# activity_monitor_v1.net
KiCad netlist of a schematic drawn in EAGLE
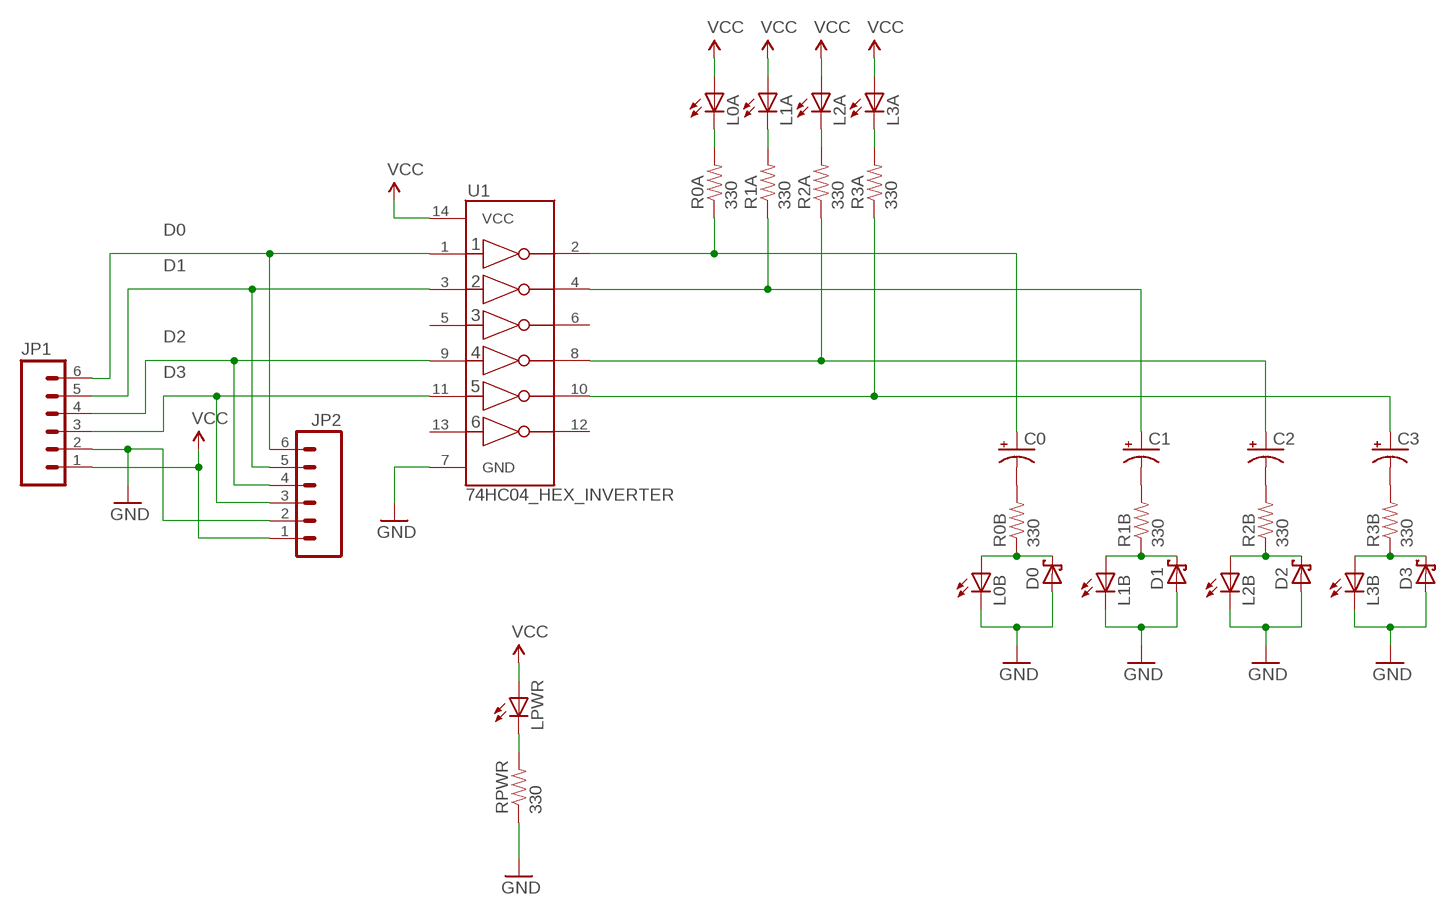
[diagram p0: schematic, sheet 1]

(export (version "E")
  (design (tool "Eeschema 10.0.6"))
  (components
    (comp (ref "C0")
      (value "CAP_POLPTH2")
      (footprint "eagle-import:CPOL-RADIAL-10UF-25V")
      (libsource (lib "eagle-import") (part "CAP_POLPTH2"))
    )
    (comp (ref "C1")
      (value "CAP_POLPTH2")
      (footprint "eagle-import:CPOL-RADIAL-10UF-25V")
      (libsource (lib "eagle-import") (part "CAP_POLPTH2"))
    )
    (comp (ref "C2")
      (value "CAP_POLPTH2")
      (footprint "eagle-import:CPOL-RADIAL-10UF-25V")
      (libsource (lib "eagle-import") (part "CAP_POLPTH2"))
    )
    (comp (ref "C3")
      (value "CAP_POLPTH2")
      (footprint "eagle-import:CPOL-RADIAL-10UF-25V")
      (libsource (lib "eagle-import") (part "CAP_POLPTH2"))
    )
    (comp (ref "D0")
      (value "SCHOTTKY-DIODEDO35-7")
      (footprint "eagle-import:DO35-7")
      (libsource (lib "eagle-import") (part "SCHOTTKY-DIODEDO35-7"))
    )
    (comp (ref "D1")
      (value "SCHOTTKY-DIODEDO35-7")
      (footprint "eagle-import:DO35-7")
      (libsource (lib "eagle-import") (part "SCHOTTKY-DIODEDO35-7"))
    )
    (comp (ref "D2")
      (value "SCHOTTKY-DIODEDO35-7")
      (footprint "eagle-import:DO35-7")
      (libsource (lib "eagle-import") (part "SCHOTTKY-DIODEDO35-7"))
    )
    (comp (ref "D3")
      (value "SCHOTTKY-DIODEDO35-7")
      (footprint "eagle-import:DO35-7")
      (libsource (lib "eagle-import") (part "SCHOTTKY-DIODEDO35-7"))
    )
    (comp (ref "JP1")
      (value "M06SIP")
      (footprint "eagle-import:1X06")
      (libsource (lib "eagle-import") (part "M06SIP"))
    )
    (comp (ref "JP2")
      (value "M06SIP")
      (footprint "eagle-import:1X06")
      (libsource (lib "eagle-import") (part "M06SIP"))
    )
    (comp (ref "L0A")
      (value "LED3MM")
      (footprint "eagle-import:LED3MM")
      (libsource (lib "eagle-import") (part "LED3MM"))
    )
    (comp (ref "L0B")
      (value "LED3MM")
      (footprint "eagle-import:LED3MM")
      (libsource (lib "eagle-import") (part "LED3MM"))
    )
    (comp (ref "L1A")
      (value "LED3MM")
      (footprint "eagle-import:LED3MM")
      (libsource (lib "eagle-import") (part "LED3MM"))
    )
    (comp (ref "L1B")
      (value "LED3MM")
      (footprint "eagle-import:LED3MM")
      (libsource (lib "eagle-import") (part "LED3MM"))
    )
    (comp (ref "L2A")
      (value "LED3MM")
      (footprint "eagle-import:LED3MM")
      (libsource (lib "eagle-import") (part "LED3MM"))
    )
    (comp (ref "L2B")
      (value "LED3MM")
      (footprint "eagle-import:LED3MM")
      (libsource (lib "eagle-import") (part "LED3MM"))
    )
    (comp (ref "L3A")
      (value "LED3MM")
      (footprint "eagle-import:LED3MM")
      (libsource (lib "eagle-import") (part "LED3MM"))
    )
    (comp (ref "L3B")
      (value "LED3MM")
      (footprint "eagle-import:LED3MM")
      (libsource (lib "eagle-import") (part "LED3MM"))
    )
    (comp (ref "LPWR")
      (value "LED3MM")
      (footprint "eagle-import:LED3MM")
      (libsource (lib "eagle-import") (part "LED3MM"))
    )
    (comp (ref "R0A")
      (value "330")
      (footprint "eagle-import:AXIAL-0.4")
      (libsource (lib "eagle-import") (part "RESISTORPTH-1/4W"))
    )
    (comp (ref "R0B")
      (value "330")
      (footprint "eagle-import:AXIAL-0.4")
      (libsource (lib "eagle-import") (part "RESISTORPTH-1/4W"))
    )
    (comp (ref "R1A")
      (value "330")
      (footprint "eagle-import:AXIAL-0.4")
      (libsource (lib "eagle-import") (part "RESISTORPTH-1/4W"))
    )
    (comp (ref "R1B")
      (value "330")
      (footprint "eagle-import:AXIAL-0.4")
      (libsource (lib "eagle-import") (part "RESISTORPTH-1/4W"))
    )
    (comp (ref "R2A")
      (value "330")
      (footprint "eagle-import:AXIAL-0.4")
      (libsource (lib "eagle-import") (part "RESISTORPTH-1/4W"))
    )
    (comp (ref "R2B")
      (value "330")
      (footprint "eagle-import:AXIAL-0.4")
      (libsource (lib "eagle-import") (part "RESISTORPTH-1/4W"))
    )
    (comp (ref "R3A")
      (value "330")
      (footprint "eagle-import:AXIAL-0.4")
      (libsource (lib "eagle-import") (part "RESISTORPTH-1/4W"))
    )
    (comp (ref "R3B")
      (value "330")
      (footprint "eagle-import:AXIAL-0.4")
      (libsource (lib "eagle-import") (part "RESISTORPTH-1/4W"))
    )
    (comp (ref "RPWR")
      (value "330")
      (footprint "eagle-import:AXIAL-0.4")
      (libsource (lib "eagle-import") (part "RESISTORPTH-1/4W"))
    )
    (comp (ref "U1")
      (value "74HC04_HEX_INVERTER")
      (footprint "eagle-import:DIL14")
      (libsource (lib "eagle-import") (part "74HC04_HEX_INVERTER"))
    )
  )
  (nets
    (net (code "1") (name "/D0") (class "Default")
      (node (ref "JP1") (pin "6") (pinfunction "6_6") (pintype "passive"))
      (node (ref "JP2") (pin "6") (pinfunction "6_6") (pintype "passive"))
      (node (ref "U1") (pin "1") (pinfunction "1A_1") (pintype "input"))
    )
    (net (code "2") (name "/D1") (class "Default")
      (node (ref "JP1") (pin "5") (pinfunction "5_5") (pintype "passive"))
      (node (ref "JP2") (pin "5") (pinfunction "5_5") (pintype "passive"))
      (node (ref "U1") (pin "3") (pinfunction "2A_3") (pintype "input"))
    )
    (net (code "3") (name "/D2") (class "Default")
      (node (ref "JP1") (pin "4") (pinfunction "4_4") (pintype "passive"))
      (node (ref "JP2") (pin "4") (pinfunction "4_4") (pintype "passive"))
      (node (ref "U1") (pin "9") (pinfunction "4A_9") (pintype "input"))
    )
    (net (code "4") (name "/D3") (class "Default")
      (node (ref "JP1") (pin "3") (pinfunction "3_3") (pintype "passive"))
      (node (ref "JP2") (pin "3") (pinfunction "3_3") (pintype "passive"))
      (node (ref "U1") (pin "11") (pinfunction "5A_11") (pintype "input"))
    )
    (net (code "5") (name "GND") (class "Default")
      (node (ref "D0") (pin "A") (pinfunction "A_A") (pintype "passive"))
      (node (ref "D1") (pin "A") (pinfunction "A_A") (pintype "passive"))
      (node (ref "D2") (pin "A") (pinfunction "A_A") (pintype "passive"))
      (node (ref "D3") (pin "A") (pinfunction "A_A") (pintype "passive"))
      (node (ref "JP1") (pin "2") (pinfunction "2_2") (pintype "passive"))
      (node (ref "JP2") (pin "2") (pinfunction "2_2") (pintype "passive"))
      (node (ref "L0B") (pin "K") (pinfunction "C_K") (pintype "passive"))
      (node (ref "L1B") (pin "K") (pinfunction "C_K") (pintype "passive"))
      (node (ref "L2B") (pin "K") (pinfunction "C_K") (pintype "passive"))
      (node (ref "L3B") (pin "K") (pinfunction "C_K") (pintype "passive"))
      (node (ref "RPWR") (pin "P$1") (pinfunction "1_P$1") (pintype "passive"))
      (node (ref "U1") (pin "7") (pinfunction "GND_7") (pintype "power_in"))
    )
    (net (code "6") (name "Net-(C0-+)") (class "Default")
      (node (ref "C0") (pin "1") (pinfunction "+_1") (pintype "passive"))
      (node (ref "R0A") (pin "P$1") (pinfunction "1_P$1") (pintype "passive"))
      (node (ref "U1") (pin "2") (pinfunction "1Y_2") (pintype "output"))
    )
    (net (code "7") (name "Net-(C0--)") (class "Default")
      (node (ref "C0") (pin "2") (pinfunction "-_2") (pintype "passive"))
      (node (ref "R0B") (pin "P$2") (pinfunction "2_P$2") (pintype "passive"))
    )
    (net (code "8") (name "Net-(C1-+)") (class "Default")
      (node (ref "C1") (pin "1") (pinfunction "+_1") (pintype "passive"))
      (node (ref "R1A") (pin "P$1") (pinfunction "1_P$1") (pintype "passive"))
      (node (ref "U1") (pin "4") (pinfunction "2Y_4") (pintype "output"))
    )
    (net (code "9") (name "Net-(C1--)") (class "Default")
      (node (ref "C1") (pin "2") (pinfunction "-_2") (pintype "passive"))
      (node (ref "R1B") (pin "P$2") (pinfunction "2_P$2") (pintype "passive"))
    )
    (net (code "10") (name "Net-(C2-+)") (class "Default")
      (node (ref "C2") (pin "1") (pinfunction "+_1") (pintype "passive"))
      (node (ref "R2A") (pin "P$1") (pinfunction "1_P$1") (pintype "passive"))
      (node (ref "U1") (pin "8") (pinfunction "4Y_8") (pintype "output"))
    )
    (net (code "11") (name "Net-(C2--)") (class "Default")
      (node (ref "C2") (pin "2") (pinfunction "-_2") (pintype "passive"))
      (node (ref "R2B") (pin "P$2") (pinfunction "2_P$2") (pintype "passive"))
    )
    (net (code "12") (name "Net-(C3-+)") (class "Default")
      (node (ref "C3") (pin "1") (pinfunction "+_1") (pintype "passive"))
      (node (ref "R3A") (pin "P$1") (pinfunction "1_P$1") (pintype "passive"))
      (node (ref "U1") (pin "10") (pinfunction "5Y_10") (pintype "output"))
    )
    (net (code "13") (name "Net-(C3--)") (class "Default")
      (node (ref "C3") (pin "2") (pinfunction "-_2") (pintype "passive"))
      (node (ref "R3B") (pin "P$2") (pinfunction "2_P$2") (pintype "passive"))
    )
    (net (code "14") (name "Net-(L0A-C)") (class "Default")
      (node (ref "L0A") (pin "K") (pinfunction "C_K") (pintype "passive"))
      (node (ref "R0A") (pin "P$2") (pinfunction "2_P$2") (pintype "passive"))
    )
    (net (code "15") (name "Net-(L1A-C)") (class "Default")
      (node (ref "L1A") (pin "K") (pinfunction "C_K") (pintype "passive"))
      (node (ref "R1A") (pin "P$2") (pinfunction "2_P$2") (pintype "passive"))
    )
    (net (code "16") (name "Net-(L2A-C)") (class "Default")
      (node (ref "L2A") (pin "K") (pinfunction "C_K") (pintype "passive"))
      (node (ref "R2A") (pin "P$2") (pinfunction "2_P$2") (pintype "passive"))
    )
    (net (code "17") (name "Net-(L3A-C)") (class "Default")
      (node (ref "L3A") (pin "K") (pinfunction "C_K") (pintype "passive"))
      (node (ref "R3A") (pin "P$2") (pinfunction "2_P$2") (pintype "passive"))
    )
    (net (code "18") (name "Net-(LPWR-C)") (class "Default")
      (node (ref "LPWR") (pin "K") (pinfunction "C_K") (pintype "passive"))
      (node (ref "RPWR") (pin "P$2") (pinfunction "2_P$2") (pintype "passive"))
    )
    (net (code "19") (name "Net-(R0B-1)") (class "Default")
      (node (ref "D0") (pin "C") (pinfunction "C_C") (pintype "passive"))
      (node (ref "L0B") (pin "A") (pinfunction "A_A") (pintype "passive"))
      (node (ref "R0B") (pin "P$1") (pinfunction "1_P$1") (pintype "passive"))
    )
    (net (code "20") (name "Net-(R1B-1)") (class "Default")
      (node (ref "D1") (pin "C") (pinfunction "C_C") (pintype "passive"))
      (node (ref "L1B") (pin "A") (pinfunction "A_A") (pintype "passive"))
      (node (ref "R1B") (pin "P$1") (pinfunction "1_P$1") (pintype "passive"))
    )
    (net (code "21") (name "Net-(R2B-1)") (class "Default")
      (node (ref "D2") (pin "C") (pinfunction "C_C") (pintype "passive"))
      (node (ref "L2B") (pin "A") (pinfunction "A_A") (pintype "passive"))
      (node (ref "R2B") (pin "P$1") (pinfunction "1_P$1") (pintype "passive"))
    )
    (net (code "22") (name "Net-(R3B-1)") (class "Default")
      (node (ref "D3") (pin "C") (pinfunction "C_C") (pintype "passive"))
      (node (ref "L3B") (pin "A") (pinfunction "A_A") (pintype "passive"))
      (node (ref "R3B") (pin "P$1") (pinfunction "1_P$1") (pintype "passive"))
    )
    (net (code "23") (name "VCC") (class "Default")
      (node (ref "JP1") (pin "1") (pinfunction "1_1") (pintype "passive"))
      (node (ref "JP2") (pin "1") (pinfunction "1_1") (pintype "passive"))
      (node (ref "L0A") (pin "A") (pinfunction "A_A") (pintype "passive"))
      (node (ref "L1A") (pin "A") (pinfunction "A_A") (pintype "passive"))
      (node (ref "L2A") (pin "A") (pinfunction "A_A") (pintype "passive"))
      (node (ref "L3A") (pin "A") (pinfunction "A_A") (pintype "passive"))
      (node (ref "LPWR") (pin "A") (pinfunction "A_A") (pintype "passive"))
      (node (ref "U1") (pin "14") (pinfunction "VCC_14") (pintype "power_in"))
    )
    (net (code "24") (name "unconnected-(U1-3A-Pad5)") (class "Default")
      (node (ref "U1") (pin "5") (pinfunction "3A_5") (pintype "input"))
    )
    (net (code "25") (name "unconnected-(U1-3Y-Pad6)") (class "Default")
      (node (ref "U1") (pin "6") (pinfunction "3Y_6") (pintype "output"))
    )
    (net (code "26") (name "unconnected-(U1-6A-Pad13)") (class "Default")
      (node (ref "U1") (pin "13") (pinfunction "6A_13") (pintype "input"))
    )
    (net (code "27") (name "unconnected-(U1-6Y-Pad12)") (class "Default")
      (node (ref "U1") (pin "12") (pinfunction "6Y_12") (pintype "output"))
    )
  )
)
